# NguyenLy.net
KiCad netlist of a schematic drawn in Altium Designer
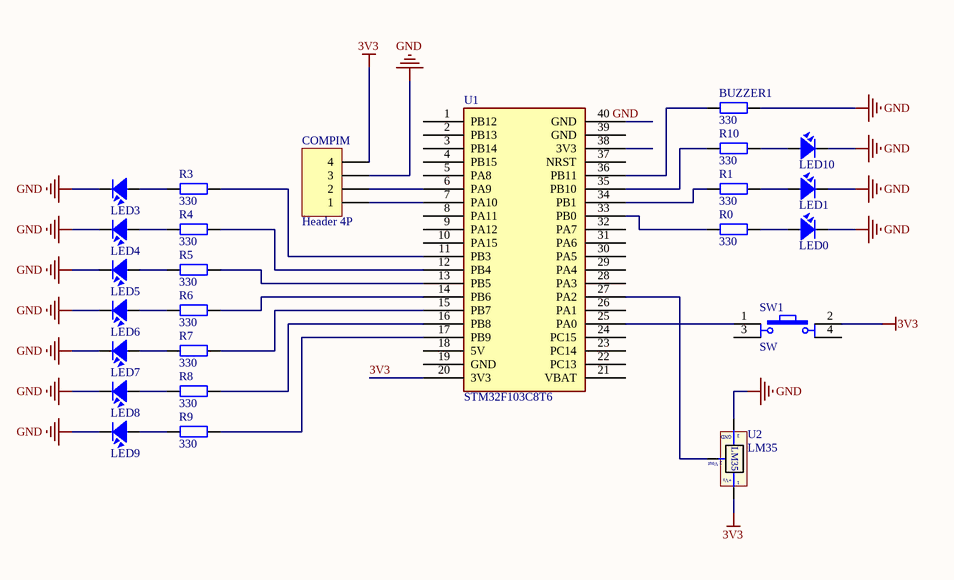
[diagram p0: NguyenLy.SchDoc]

(export (version "E")
  (design (tool "Eeschema 10.0.6"))
  (components
    (comp (ref "BUZZER1")
      (value "330")
      (footprint "R1/4W")
      (description "Resistor 1/4W")
      (libsource (lib "syhaunguyen") (part "R1/4W"))
    )
    (comp (ref "COMPIM")
      (value "Header 4P")
      (footprint "HDR1X4")
      (description "Header, 4 Pin Pitch 2.54mm")
      (fields (field (name "MPN") "S1012EC-40-ND"))
      (libsource (lib "BYTECH_HW_LIB_2019") (part "Header 4x1"))
    )
    (comp (ref "LED0")
      (value "LED")
      (footprint "LED-3")
      (description "LED Single colour Green and Red")
      (libsource (lib "syhaunguyen") (part "LED"))
    )
    (comp (ref "LED1")
      (value "LED")
      (footprint "LED-3")
      (description "LED Single colour Green and Red")
      (libsource (lib "syhaunguyen") (part "LED"))
    )
    (comp (ref "LED3")
      (value "LED")
      (footprint "LED-3")
      (description "LED Single colour Green and Red")
      (libsource (lib "syhaunguyen") (part "LED"))
    )
    (comp (ref "LED4")
      (value "LED")
      (footprint "LED-3")
      (description "LED Single colour Green and Red")
      (libsource (lib "syhaunguyen") (part "LED"))
    )
    (comp (ref "LED5")
      (value "LED")
      (footprint "LED-3")
      (description "LED Single colour Green and Red")
      (libsource (lib "syhaunguyen") (part "LED"))
    )
    (comp (ref "LED6")
      (value "LED")
      (footprint "LED-3")
      (description "LED Single colour Green and Red")
      (libsource (lib "syhaunguyen") (part "LED"))
    )
    (comp (ref "LED7")
      (value "LED")
      (footprint "LED-3")
      (description "LED Single colour Green and Red")
      (libsource (lib "syhaunguyen") (part "LED"))
    )
    (comp (ref "LED8")
      (value "LED")
      (footprint "LED-3")
      (description "LED Single colour Green and Red")
      (libsource (lib "syhaunguyen") (part "LED"))
    )
    (comp (ref "LED9")
      (value "LED")
      (footprint "LED-3")
      (description "LED Single colour Green and Red")
      (libsource (lib "syhaunguyen") (part "LED"))
    )
    (comp (ref "LED10")
      (value "LED")
      (footprint "LED-3")
      (description "LED Single colour Green and Red")
      (libsource (lib "syhaunguyen") (part "LED"))
    )
    (comp (ref "R0")
      (value "330")
      (footprint "R1/4W")
      (description "Resistor 1/4W")
      (libsource (lib "syhaunguyen") (part "R1/4W"))
    )
    (comp (ref "R1")
      (value "330")
      (footprint "R1/4W")
      (description "Resistor 1/4W")
      (libsource (lib "syhaunguyen") (part "R1/4W"))
    )
    (comp (ref "R3")
      (value "330")
      (footprint "R1/4W")
      (description "Resistor 1/4W")
      (libsource (lib "syhaunguyen") (part "R1/4W"))
    )
    (comp (ref "R4")
      (value "330")
      (footprint "R1/4W")
      (description "Resistor 1/4W")
      (libsource (lib "syhaunguyen") (part "R1/4W"))
    )
    (comp (ref "R5")
      (value "330")
      (footprint "R1/4W")
      (description "Resistor 1/4W")
      (libsource (lib "syhaunguyen") (part "R1/4W"))
    )
    (comp (ref "R6")
      (value "330")
      (footprint "R1/4W")
      (description "Resistor 1/4W")
      (libsource (lib "syhaunguyen") (part "R1/4W"))
    )
    (comp (ref "R7")
      (value "330")
      (footprint "R1/4W")
      (description "Resistor 1/4W")
      (libsource (lib "syhaunguyen") (part "R1/4W"))
    )
    (comp (ref "R8")
      (value "330")
      (footprint "R1/4W")
      (description "Resistor 1/4W")
      (libsource (lib "syhaunguyen") (part "R1/4W"))
    )
    (comp (ref "R9")
      (value "330")
      (footprint "R1/4W")
      (description "Resistor 1/4W")
      (libsource (lib "syhaunguyen") (part "R1/4W"))
    )
    (comp (ref "R10")
      (value "330")
      (footprint "R1/4W")
      (description "Resistor 1/4W")
      (libsource (lib "syhaunguyen") (part "R1/4W"))
    )
    (comp (ref "SW1")
      (value "SW")
      (footprint "SW4")
      (description "Switch button 4 pin")
      (libsource (lib "syhaunguyen") (part "SW4"))
    )
    (comp (ref "U1")
      (value "STM32F103C8T6")
      (footprint "Stm32 BluePill")
      (description "Designed By @Alixahedi")
      (libsource (lib "Stm32 Blue Pill") (part "BluePill"))
    )
    (comp (ref "U2")
      (value "LM35")
      (footprint "QTO-92")
      (description "Teminal")
      (libsource (lib "syhaunguyen") (part "LM35"))
    )
  )
  (nets
    (net (code "1") (name "3V3") (class "Default")
      (node (ref "COMPIM") (pin "4") (pinfunction "4_4") (pintype "passive"))
      (node (ref "SW1") (pin "2") (pintype "passive"))
      (node (ref "U1") (pin "20") (pinfunction "3V3_20") (pintype "passive"))
      (node (ref "U2") (pin "1") (pinfunction "+Vs_1") (pintype "passive"))
    )
    (net (code "2") (name "GND") (class "Default")
      (node (ref "BUZZER1") (pin "1") (pinfunction "1_1") (pintype "passive"))
      (node (ref "COMPIM") (pin "3") (pinfunction "3_3") (pintype "passive"))
      (node (ref "LED0") (pin "2") (pinfunction "2_2") (pintype "passive"))
      (node (ref "LED1") (pin "2") (pinfunction "2_2") (pintype "passive"))
      (node (ref "LED10") (pin "2") (pinfunction "2_2") (pintype "passive"))
      (node (ref "LED3") (pin "2") (pinfunction "2_2") (pintype "passive"))
      (node (ref "LED4") (pin "2") (pinfunction "2_2") (pintype "passive"))
      (node (ref "LED5") (pin "2") (pinfunction "2_2") (pintype "passive"))
      (node (ref "LED6") (pin "2") (pinfunction "2_2") (pintype "passive"))
      (node (ref "LED7") (pin "2") (pinfunction "2_2") (pintype "passive"))
      (node (ref "LED8") (pin "2") (pinfunction "2_2") (pintype "passive"))
      (node (ref "LED9") (pin "2") (pinfunction "2_2") (pintype "passive"))
      (node (ref "U2") (pin "3") (pinfunction "-_3") (pintype "passive"))
    )
    (net (code "3") (name "Net-(LED0-Pad1)") (class "Default")
      (node (ref "LED0") (pin "1") (pinfunction "1_1") (pintype "passive"))
      (node (ref "R0") (pin "1") (pinfunction "1_1") (pintype "passive"))
    )
    (net (code "4") (name "Net-(LED1-Pad1)") (class "Default")
      (node (ref "LED1") (pin "1") (pinfunction "1_1") (pintype "passive"))
      (node (ref "R1") (pin "1") (pinfunction "1_1") (pintype "passive"))
    )
    (net (code "5") (name "Net-(LED3-Pad1)") (class "Default")
      (node (ref "LED3") (pin "1") (pinfunction "1_1") (pintype "passive"))
      (node (ref "R3") (pin "1") (pinfunction "1_1") (pintype "passive"))
    )
    (net (code "6") (name "Net-(LED4-Pad1)") (class "Default")
      (node (ref "LED4") (pin "1") (pinfunction "1_1") (pintype "passive"))
      (node (ref "R4") (pin "1") (pinfunction "1_1") (pintype "passive"))
    )
    (net (code "7") (name "Net-(LED5-Pad1)") (class "Default")
      (node (ref "LED5") (pin "1") (pinfunction "1_1") (pintype "passive"))
      (node (ref "R5") (pin "1") (pinfunction "1_1") (pintype "passive"))
    )
    (net (code "8") (name "Net-(LED6-Pad1)") (class "Default")
      (node (ref "LED6") (pin "1") (pinfunction "1_1") (pintype "passive"))
      (node (ref "R6") (pin "1") (pinfunction "1_1") (pintype "passive"))
    )
    (net (code "9") (name "Net-(LED7-Pad1)") (class "Default")
      (node (ref "LED7") (pin "1") (pinfunction "1_1") (pintype "passive"))
      (node (ref "R7") (pin "1") (pinfunction "1_1") (pintype "passive"))
    )
    (net (code "10") (name "Net-(LED8-Pad1)") (class "Default")
      (node (ref "LED8") (pin "1") (pinfunction "1_1") (pintype "passive"))
      (node (ref "R8") (pin "1") (pinfunction "1_1") (pintype "passive"))
    )
    (net (code "11") (name "Net-(LED9-Pad1)") (class "Default")
      (node (ref "LED9") (pin "1") (pinfunction "1_1") (pintype "passive"))
      (node (ref "R9") (pin "1") (pinfunction "1_1") (pintype "passive"))
    )
    (net (code "12") (name "Net-(LED10-Pad1)") (class "Default")
      (node (ref "LED10") (pin "1") (pinfunction "1_1") (pintype "passive"))
      (node (ref "R10") (pin "1") (pinfunction "1_1") (pintype "passive"))
    )
    (net (code "13") (name "Net-(U1-PA0)") (class "Default")
      (node (ref "SW1") (pin "1") (pintype "passive"))
      (node (ref "U1") (pin "25") (pinfunction "PA0_25") (pintype "passive"))
    )
    (net (code "14") (name "Net-(U1-PA2)") (class "Default")
      (node (ref "U1") (pin "27") (pinfunction "PA2_27") (pintype "passive"))
      (node (ref "U2") (pin "2") (pinfunction "Vout_2") (pintype "passive"))
    )
    (net (code "15") (name "Net-(U1-PA9)") (class "Default")
      (node (ref "COMPIM") (pin "2") (pinfunction "2_2") (pintype "passive"))
      (node (ref "U1") (pin "6") (pinfunction "PA9_6") (pintype "passive"))
    )
    (net (code "16") (name "Net-(U1-PA10)") (class "Default")
      (node (ref "COMPIM") (pin "1") (pinfunction "1_1") (pintype "passive"))
      (node (ref "U1") (pin "7") (pinfunction "PA10_7") (pintype "passive"))
    )
    (net (code "17") (name "Net-(U1-PB0)") (class "Default")
      (node (ref "R0") (pin "2") (pinfunction "2_2") (pintype "passive"))
      (node (ref "U1") (pin "33") (pinfunction "PB0_33") (pintype "passive"))
    )
    (net (code "18") (name "Net-(U1-PB1)") (class "Default")
      (node (ref "R1") (pin "2") (pinfunction "2_2") (pintype "passive"))
      (node (ref "U1") (pin "34") (pinfunction "PB1_34") (pintype "passive"))
    )
    (net (code "19") (name "Net-(U1-PB3)") (class "Default")
      (node (ref "R3") (pin "2") (pinfunction "2_2") (pintype "passive"))
      (node (ref "U1") (pin "11") (pinfunction "PB3_11") (pintype "passive"))
    )
    (net (code "20") (name "Net-(U1-PB4)") (class "Default")
      (node (ref "R4") (pin "2") (pinfunction "2_2") (pintype "passive"))
      (node (ref "U1") (pin "12") (pinfunction "PB4_12") (pintype "passive"))
    )
    (net (code "21") (name "Net-(U1-PB5)") (class "Default")
      (node (ref "R5") (pin "2") (pinfunction "2_2") (pintype "passive"))
      (node (ref "U1") (pin "13") (pinfunction "PB5_13") (pintype "passive"))
    )
    (net (code "22") (name "Net-(U1-PB6)") (class "Default")
      (node (ref "R6") (pin "2") (pinfunction "2_2") (pintype "passive"))
      (node (ref "U1") (pin "14") (pinfunction "PB6_14") (pintype "passive"))
    )
    (net (code "23") (name "Net-(U1-PB7)") (class "Default")
      (node (ref "R7") (pin "2") (pinfunction "2_2") (pintype "passive"))
      (node (ref "U1") (pin "15") (pinfunction "PB7_15") (pintype "passive"))
    )
    (net (code "24") (name "Net-(U1-PB8)") (class "Default")
      (node (ref "R8") (pin "2") (pinfunction "2_2") (pintype "passive"))
      (node (ref "U1") (pin "16") (pinfunction "PB8_16") (pintype "passive"))
    )
    (net (code "25") (name "Net-(U1-PB9)") (class "Default")
      (node (ref "R9") (pin "2") (pinfunction "2_2") (pintype "passive"))
      (node (ref "U1") (pin "17") (pinfunction "PB9_17") (pintype "passive"))
    )
    (net (code "26") (name "Net-(U1-PB10)") (class "Default")
      (node (ref "R10") (pin "2") (pinfunction "2_2") (pintype "passive"))
      (node (ref "U1") (pin "35") (pinfunction "PB10_35") (pintype "passive"))
    )
    (net (code "27") (name "Net-(U1-PB11)") (class "Default")
      (node (ref "BUZZER1") (pin "2") (pinfunction "2_2") (pintype "passive"))
      (node (ref "U1") (pin "36") (pinfunction "PB11_36") (pintype "passive"))
    )
    (net (code "28") (name "unconnected-(SW1-Pad3)") (class "Default")
      (node (ref "SW1") (pin "3") (pintype "passive"))
    )
    (net (code "29") (name "unconnected-(SW1-Pad4)") (class "Default")
      (node (ref "SW1") (pin "4") (pintype "passive"))
    )
    (net (code "30") (name "unconnected-(U1-3V3-Pad38)") (class "Default")
      (node (ref "U1") (pin "38") (pinfunction "3V3_38") (pintype "passive"))
    )
    (net (code "31") (name "unconnected-(U1-5V-Pad18)") (class "Default")
      (node (ref "U1") (pin "18") (pinfunction "5V_18") (pintype "passive"))
    )
    (net (code "32") (name "unconnected-(U1-GND-Pad19)") (class "Default")
      (node (ref "U1") (pin "19") (pinfunction "GND_19") (pintype "passive"))
    )
    (net (code "33") (name "unconnected-(U1-GND-Pad39)") (class "Default")
      (node (ref "U1") (pin "39") (pinfunction "GND_39") (pintype "passive"))
    )
    (net (code "34") (name "unconnected-(U1-GND-Pad40)") (class "Default")
      (node (ref "U1") (pin "40") (pinfunction "GND_40") (pintype "passive"))
    )
    (net (code "35") (name "unconnected-(U1-NRST-Pad37)") (class "Default")
      (node (ref "U1") (pin "37") (pinfunction "NRST_37") (pintype "passive"))
    )
    (net (code "36") (name "unconnected-(U1-PA1-Pad26)") (class "Default")
      (node (ref "U1") (pin "26") (pinfunction "PA1_26") (pintype "passive"))
    )
    (net (code "37") (name "unconnected-(U1-PA3-Pad28)") (class "Default")
      (node (ref "U1") (pin "28") (pinfunction "PA3_28") (pintype "passive"))
    )
    (net (code "38") (name "unconnected-(U1-PA4-Pad29)") (class "Default")
      (node (ref "U1") (pin "29") (pinfunction "PA4_29") (pintype "passive"))
    )
    (net (code "39") (name "unconnected-(U1-PA5-Pad30)") (class "Default")
      (node (ref "U1") (pin "30") (pinfunction "PA5_30") (pintype "passive"))
    )
    (net (code "40") (name "unconnected-(U1-PA6-Pad31)") (class "Default")
      (node (ref "U1") (pin "31") (pinfunction "PA6_31") (pintype "passive"))
    )
    (net (code "41") (name "unconnected-(U1-PA7-Pad32)") (class "Default")
      (node (ref "U1") (pin "32") (pinfunction "PA7_32") (pintype "passive"))
    )
    (net (code "42") (name "unconnected-(U1-PA8-Pad5)") (class "Default")
      (node (ref "U1") (pin "5") (pinfunction "PA8_5") (pintype "passive"))
    )
    (net (code "43") (name "unconnected-(U1-PA11-Pad8)") (class "Default")
      (node (ref "U1") (pin "8") (pinfunction "PA11_8") (pintype "passive"))
    )
    (net (code "44") (name "unconnected-(U1-PA12-Pad9)") (class "Default")
      (node (ref "U1") (pin "9") (pinfunction "PA12_9") (pintype "passive"))
    )
    (net (code "45") (name "unconnected-(U1-PA15-Pad10)") (class "Default")
      (node (ref "U1") (pin "10") (pinfunction "PA15_10") (pintype "passive"))
    )
    (net (code "46") (name "unconnected-(U1-PB12-Pad1)") (class "Default")
      (node (ref "U1") (pin "1") (pinfunction "PB12_1") (pintype "passive"))
    )
    (net (code "47") (name "unconnected-(U1-PB13-Pad2)") (class "Default")
      (node (ref "U1") (pin "2") (pinfunction "PB13_2") (pintype "passive"))
    )
    (net (code "48") (name "unconnected-(U1-PB14-Pad3)") (class "Default")
      (node (ref "U1") (pin "3") (pinfunction "PB14_3") (pintype "passive"))
    )
    (net (code "49") (name "unconnected-(U1-PB15-Pad4)") (class "Default")
      (node (ref "U1") (pin "4") (pinfunction "PB15_4") (pintype "passive"))
    )
    (net (code "50") (name "unconnected-(U1-PC13-Pad22)") (class "Default")
      (node (ref "U1") (pin "22") (pinfunction "PC13_22") (pintype "passive"))
    )
    (net (code "51") (name "unconnected-(U1-PC14-Pad23)") (class "Default")
      (node (ref "U1") (pin "23") (pinfunction "PC14_23") (pintype "passive"))
    )
    (net (code "52") (name "unconnected-(U1-PC15-Pad24)") (class "Default")
      (node (ref "U1") (pin "24") (pinfunction "PC15_24") (pintype "passive"))
    )
    (net (code "53") (name "unconnected-(U1-VBAT-Pad21)") (class "Default")
      (node (ref "U1") (pin "21") (pinfunction "VBAT_21") (pintype "passive"))
    )
  )
)
